# Fastino_FPGA_Config.net
KiCad netlist of a schematic drawn in Altium Designer
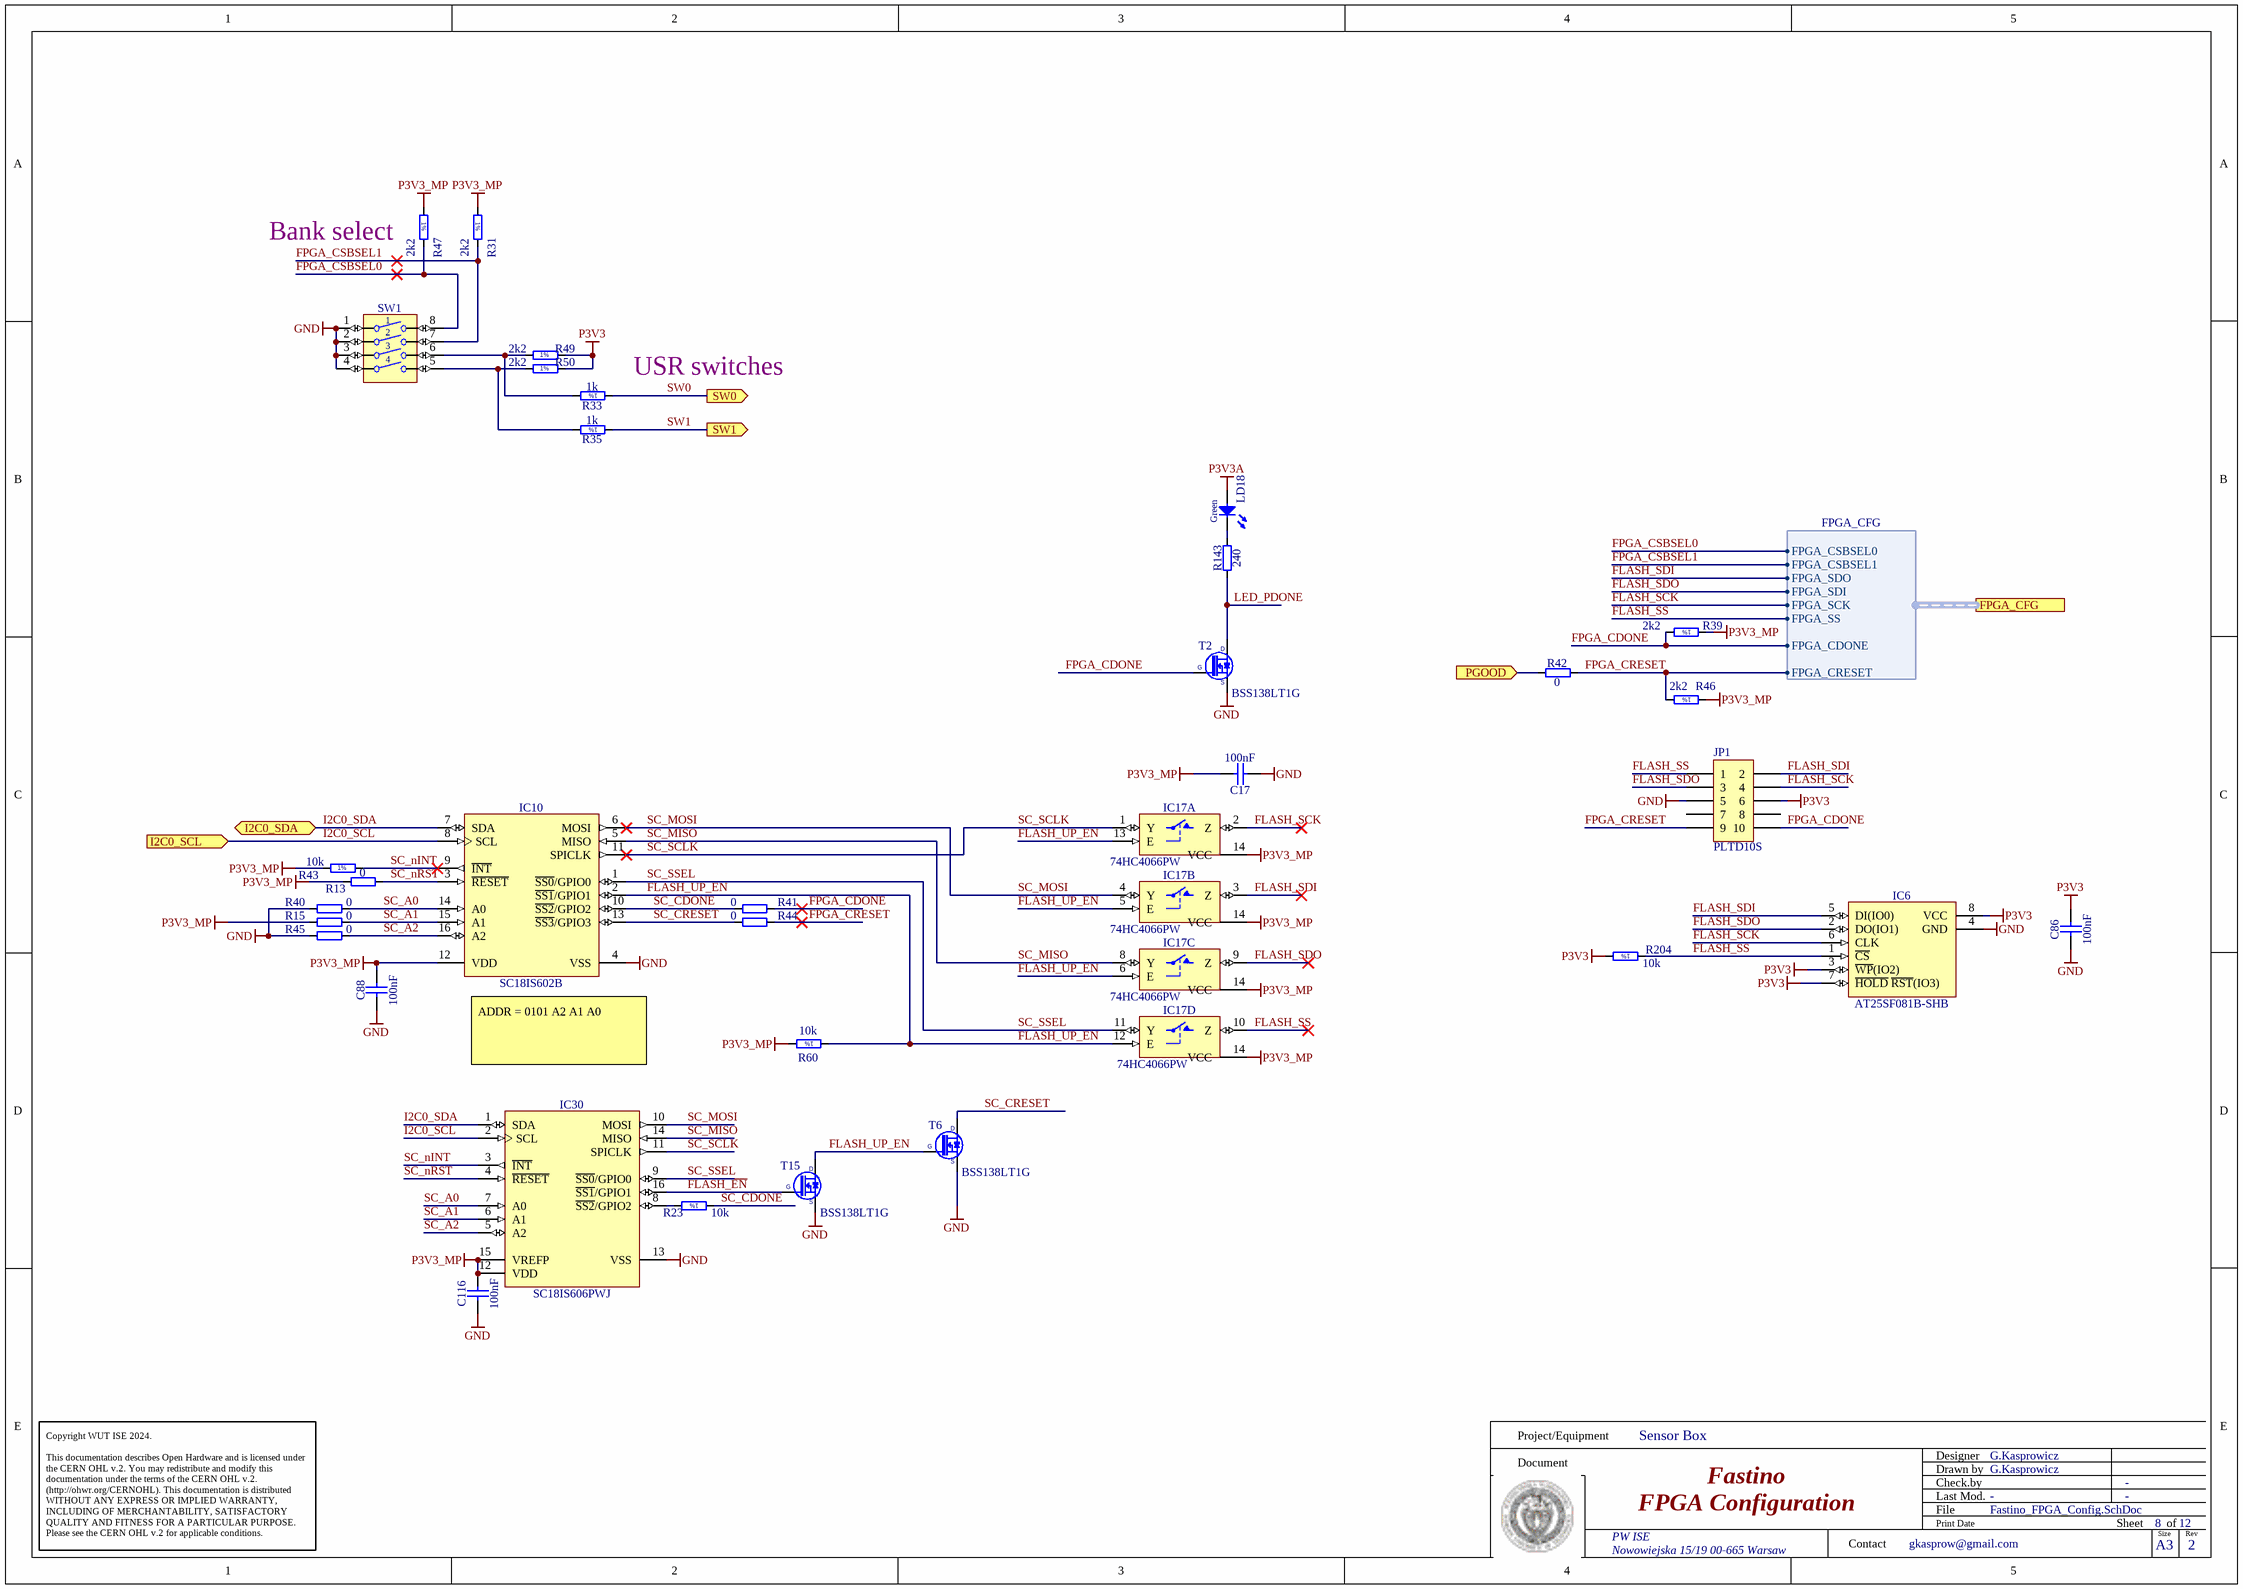
[diagram p0: Fastino_FPGA_Config.SchDoc]

(export (version "E")
  (design (tool "Eeschema 10.0.6"))
  (components
    (comp (ref "C17")
      (value "100nF")
      (footprint "CAPC1005X55N")
      (description "Non-polarised capacitor")
      (fields
        (field (name "PART NUMBER") "CC0402_100NF_16V_10%_X5R")
        (field (name "VOLTAGE") "16V")
        (field (name "AUTHOR") "CERN DEM JLC")
      )
      (libsource (lib "Capacitors") (part "Capacitor - non polarized"))
    )
    (comp (ref "C86")
      (value "100nF")
      (footprint "CAPC1005X55N")
      (description "Non-polarised capacitor")
      (fields
        (field (name "PART NUMBER") "CC0402_100NF_16V_10%_X5R")
        (field (name "VOLTAGE") "16V")
        (field (name "AUTHOR") "CERN DEM JLC")
      )
      (libsource (lib "Capacitors") (part "Capacitor - non polarized"))
    )
    (comp (ref "C88")
      (value "100nF")
      (footprint "CAPC1005X55N")
      (description "Non-polarised capacitor")
      (fields
        (field (name "PART NUMBER") "CC0402_100NF_16V_10%_X5R")
        (field (name "VOLTAGE") "16V")
        (field (name "AUTHOR") "CERN DEM JLC")
      )
      (libsource (lib "Capacitors") (part "Capacitor - non polarized"))
    )
    (comp (ref "C116")
      (value "100nF")
      (footprint "CAPC1005X55N")
      (description "Non-polarised capacitor")
      (fields
        (field (name "PART NUMBER") "CC0402_100NF_16V_10%_X5R")
        (field (name "VOLTAGE") "16V")
        (field (name "AUTHOR") "CERN DEM JLC")
      )
      (libsource (lib "Capacitors") (part "Capacitor - non polarized"))
    )
    (comp (ref "IC6")
      (value "AT25SF081B-SHB")
      (footprint "SOIC127P790X216-8N")
      (description "8M-bit Serial Flash Memory with uniform 4KB sectors and Dual/Quad SPI and QPI")
      (fields (field (name "MANUFACTURER") "Renesas") (field (name "AUTHOR") "GK"))
      (libsource (lib "ICS-logic") (part "MEM_AT25SF081B-SHB"))
    )
    (comp (ref "IC10")
      (value "SC18IS602B")
      (footprint "SOP65P640X110-16N")
      (description "I2C-bus to SPI bridge")
      (fields (field (name "MANUFACTURER") "NXP SEMICONDUCTORS") (field (name "AUTHOR") "CERN DEM MR"))
      (libsource (lib "ICs And Semiconductors") (part "SC18IS602B"))
    )
    (comp (ref "IC17")
      (value "74HC4066PW")
      (footprint "SOP65P640X110-14N")
      (fields (field (name "MANUFACTURER") "NXP SEMICONDUCTORS") (field (name "AUTHOR") "CERN DEM JLC"))
      (libsource (lib "ICs And Semiconductors") (part "4066"))
    )
    (comp (ref "IC30")
      (value "SC18IS606PWJ")
      (footprint "SOP65P640X110-16N")
      (description "I2C-bus to SPI bridge")
      (fields (field (name "MANUFACTURER") "NXP SEMICONDUCTORS") (field (name "AUTHOR") "GK"))
      (libsource (lib "ICS-logic") (part "SC18IS606PWJ"))
    )
    (comp (ref "JP1")
      (value "PLTD10S")
      (footprint "PLTD10S")
      (description "Goldpin 2.54mm, male header")
      (fields (field (name "MANUFACTURER") "Maritex"))
      (libsource (lib "LIBRARY_SCH") (part "CON_2x5 2.54 male SMT"))
    )
    (comp (ref "LD18")
      (value "Green")
      (footprint "LED_AVAGO_HSME-C120")
      (description "LED Green 1C 2A")
      (fields
        (field (name "PART NUMBER") "LED_AVAGO_HSME-C120")
        (field (name "MANUFACTURER") "AVAGO TECHNOLOGIES")
        (field (name "AUTHOR") "CERN DEM JMW")
      )
      (libsource (lib "ICs And Semiconductors") (part "LED Green 1C 2A"))
    )
    (comp (ref "R13")
      (value "0")
      (footprint "RESC1005X40N")
      (description "Resistor")
      (fields
        (field (name "PART NUMBER") "R0402_0R_JUMPER")
        (field (name "MANUFACTURER") "GENERIC")
        (field (name "AUTHOR") "CERN DEM JLC")
      )
      (libsource (lib "Resistors") (part "Resistor"))
    )
    (comp (ref "R15")
      (value "0")
      (footprint "RESC1005X40N")
      (description "Resistor")
      (fields
        (field (name "PART NUMBER") "R0402_0R_JUMPER")
        (field (name "MANUFACTURER") "GENERIC")
        (field (name "AUTHOR") "CERN DEM JLC")
      )
      (libsource (lib "Resistors") (part "Resistor"))
    )
    (comp (ref "R23")
      (value "10k")
      (footprint "RESC1005X40N")
      (description "Resistor - 1%")
      (fields
        (field (name "PART NUMBER") "R0402_10K_1%_0.0625W_100PPM")
        (field (name "POWER") "0.0625W")
        (field (name "AUTHOR") "CERN DEM JLC")
      )
      (libsource (lib "Resistors") (part "Resistor - 1%"))
    )
    (comp (ref "R31")
      (value "2k2")
      (footprint "RESC1005X40N")
      (description "Resistor - 1%")
      (fields
        (field (name "PART NUMBER") "R0402_2K2_1%_0.0625W_100PPM")
        (field (name "POWER") "0.0625W")
        (field (name "AUTHOR") "CERN DEM JLC")
      )
      (libsource (lib "Resistors") (part "Resistor - 1%"))
    )
    (comp (ref "R33")
      (value "1k")
      (footprint "RESC1005X40N")
      (description "Resistor - 1%")
      (fields
        (field (name "PART NUMBER") "R0402_1K_1%_0.0625W_100PPM")
        (field (name "POWER") "0.0625W")
        (field (name "AUTHOR") "CERN DEM JLC")
      )
      (libsource (lib "Resistors") (part "Resistor - 1%"))
    )
    (comp (ref "R35")
      (value "1k")
      (footprint "RESC1005X40N")
      (description "Resistor - 1%")
      (fields
        (field (name "PART NUMBER") "R0402_1K_1%_0.0625W_100PPM")
        (field (name "POWER") "0.0625W")
        (field (name "AUTHOR") "CERN DEM JLC")
      )
      (libsource (lib "Resistors") (part "Resistor - 1%"))
    )
    (comp (ref "R39")
      (value "2k2")
      (footprint "RESC1005X40N")
      (description "Resistor - 1%")
      (fields
        (field (name "PART NUMBER") "R0402_2K2_1%_0.0625W_100PPM")
        (field (name "POWER") "0.0625W")
        (field (name "AUTHOR") "CERN DEM JLC")
      )
      (libsource (lib "Resistors") (part "Resistor - 1%"))
    )
    (comp (ref "R40")
      (value "0")
      (footprint "RESC1005X40N")
      (description "Resistor")
      (fields
        (field (name "PART NUMBER") "R0402_0R_JUMPER")
        (field (name "MANUFACTURER") "GENERIC")
        (field (name "AUTHOR") "CERN DEM JLC")
      )
      (libsource (lib "Resistors") (part "Resistor"))
    )
    (comp (ref "R41")
      (value "0")
      (footprint "RESC1005X40N")
      (description "Resistor")
      (fields
        (field (name "PART NUMBER") "R0402_0R_JUMPER")
        (field (name "MANUFACTURER") "GENERIC")
        (field (name "AUTHOR") "CERN DEM JLC")
      )
      (libsource (lib "Resistors") (part "Resistor"))
    )
    (comp (ref "R42")
      (value "0")
      (footprint "RESC1005X40N")
      (description "Resistor")
      (fields
        (field (name "PART NUMBER") "R0402_0R_JUMPER")
        (field (name "MANUFACTURER") "GENERIC")
        (field (name "AUTHOR") "CERN DEM JLC")
      )
      (libsource (lib "Resistors") (part "Resistor"))
    )
    (comp (ref "R43")
      (value "10k")
      (footprint "RESC1005X40N")
      (description "Resistor - 1%")
      (fields
        (field (name "PART NUMBER") "R0402_10K_1%_0.0625W_100PPM")
        (field (name "POWER") "0.0625W")
        (field (name "AUTHOR") "CERN DEM JLC")
      )
      (libsource (lib "Resistors") (part "Resistor - 1%"))
    )
    (comp (ref "R44")
      (value "0")
      (footprint "RESC1005X40N")
      (description "Resistor")
      (fields
        (field (name "PART NUMBER") "R0402_0R_JUMPER")
        (field (name "MANUFACTURER") "GENERIC")
        (field (name "AUTHOR") "CERN DEM JLC")
      )
      (libsource (lib "Resistors") (part "Resistor"))
    )
    (comp (ref "R45")
      (value "0")
      (footprint "RESC1005X40N")
      (description "Resistor")
      (fields
        (field (name "PART NUMBER") "R0402_0R_JUMPER")
        (field (name "MANUFACTURER") "GENERIC")
        (field (name "AUTHOR") "CERN DEM JLC")
      )
      (libsource (lib "Resistors") (part "Resistor"))
    )
    (comp (ref "R46")
      (value "2k2")
      (footprint "RESC1005X40N")
      (description "Resistor - 1%")
      (fields
        (field (name "PART NUMBER") "R0402_2K2_1%_0.0625W_100PPM")
        (field (name "POWER") "0.0625W")
        (field (name "AUTHOR") "CERN DEM JLC")
      )
      (libsource (lib "Resistors") (part "Resistor - 1%"))
    )
    (comp (ref "R47")
      (value "2k2")
      (footprint "RESC1005X40N")
      (description "Resistor - 1%")
      (fields
        (field (name "PART NUMBER") "R0402_2K2_1%_0.0625W_100PPM")
        (field (name "POWER") "0.0625W")
        (field (name "AUTHOR") "CERN DEM JLC")
      )
      (libsource (lib "Resistors") (part "Resistor - 1%"))
    )
    (comp (ref "R49")
      (value "2k2")
      (footprint "RESC1005X40N")
      (description "Resistor - 1%")
      (fields
        (field (name "PART NUMBER") "R0402_2K2_1%_0.0625W_100PPM")
        (field (name "POWER") "0.0625W")
        (field (name "AUTHOR") "CERN DEM JLC")
      )
      (libsource (lib "Resistors") (part "Resistor - 1%"))
    )
    (comp (ref "R50")
      (value "2k2")
      (footprint "RESC1005X40N")
      (description "Resistor - 1%")
      (fields
        (field (name "PART NUMBER") "R0402_2K2_1%_0.0625W_100PPM")
        (field (name "POWER") "0.0625W")
        (field (name "AUTHOR") "CERN DEM JLC")
      )
      (libsource (lib "Resistors") (part "Resistor - 1%"))
    )
    (comp (ref "R60")
      (value "10k")
      (footprint "RESC1005X40N")
      (description "Resistor - 1%")
      (fields
        (field (name "PART NUMBER") "R0402_10K_1%_0.0625W_100PPM")
        (field (name "POWER") "0.0625W")
        (field (name "AUTHOR") "CERN DEM JLC")
      )
      (libsource (lib "Resistors") (part "Resistor - 1%"))
    )
    (comp (ref "R143")
      (value "240")
      (footprint "RESC1005X40N")
      (description "Resistor - 1%")
      (fields
        (field (name "PART NUMBER") "R0402_240R_1%_0.0625W_100PPM")
        (field (name "POWER") "0.0625W")
        (field (name "AUTHOR") "CERN DEM JLC")
      )
      (libsource (lib "Resistors") (part "Resistor - 1%"))
    )
    (comp (ref "R204")
      (value "10k")
      (footprint "RESC1005X40N")
      (description "Resistor - 1%")
      (fields
        (field (name "PART NUMBER") "R0402_10K_1%_0.0625W_100PPM")
        (field (name "POWER") "0.0625W")
        (field (name "AUTHOR") "CERN DEM JLC")
      )
      (libsource (lib "Resistors") (part "Resistor - 1%"))
    )
    (comp (ref "SW1")
      (value "Switch")
      (footprint "SW_TYCO_1571983-4")
      (description "4 Ways SPST DIP Switch")
      (fields
        (field (name "PART NUMBER") "SW_TYCO_1571983-4")
        (field (name "MANUFACTURER") "TYCO")
        (field (name "AUTHOR") "CERN DEM JLC")
      )
      (libsource (lib "Eletro-mechanical") (part "SW 4x SPST DIP Switch"))
    )
    (comp (ref "T2")
      (value "BSS138LT1G")
      (footprint "SOT95P240X110-3N")
      (description "N-CHANNEL MOSFET WITH DIODE")
      (fields (field (name "MANUFACTURER") "ON SEMICONDUCTOR") (field (name "AUTHOR") "CERN DEM JLC"))
      (libsource (lib "ICs And Semiconductors") (part "N-MOSFET-D 1G 2S 3D"))
    )
    (comp (ref "T6")
      (value "BSS138LT1G")
      (footprint "SOT95P240X110-3N")
      (description "N-CHANNEL MOSFET WITH DIODE")
      (fields (field (name "MANUFACTURER") "ON SEMICONDUCTOR") (field (name "AUTHOR") "CERN DEM JLC"))
      (libsource (lib "ICs And Semiconductors") (part "N-MOSFET-D 1G 2S 3D"))
    )
    (comp (ref "T15")
      (value "BSS138LT1G")
      (footprint "SOT95P240X110-3N")
      (description "N-CHANNEL MOSFET WITH DIODE")
      (fields (field (name "MANUFACTURER") "ON SEMICONDUCTOR") (field (name "AUTHOR") "CERN DEM JLC"))
      (libsource (lib "ICs And Semiconductors") (part "N-MOSFET-D 1G 2S 3D"))
    )
  )
  (nets
    (net (code "2") (name "/FLASH_SCK") (class "Default")
      (node (ref "IC17") (pin "2") (pinfunction "Z_2") (pintype "bidirectional"))
      (node (ref "IC6") (pin "6") (pinfunction "CLK_6") (pintype "input"))
      (node (ref "JP1") (pin "4") (pinfunction "4_4") (pintype "passive"))
    )
    (net (code "3") (name "/FLASH_SDI") (class "Default")
      (node (ref "IC17") (pin "3") (pinfunction "Z_3") (pintype "bidirectional"))
      (node (ref "IC6") (pin "5") (pinfunction "DI(IO0)_5") (pintype "bidirectional"))
      (node (ref "JP1") (pin "2") (pinfunction "2_2") (pintype "passive"))
    )
    (net (code "4") (name "/FLASH_SDO") (class "Default")
      (node (ref "IC17") (pin "9") (pinfunction "Z_9") (pintype "bidirectional"))
      (node (ref "IC6") (pin "2") (pinfunction "DO(IO1)_2") (pintype "bidirectional"))
      (node (ref "JP1") (pin "3") (pinfunction "3_3") (pintype "passive"))
    )
    (net (code "5") (name "/FLASH_SS") (class "Default")
      (node (ref "IC17") (pin "10") (pinfunction "Z_10") (pintype "bidirectional"))
      (node (ref "IC6") (pin "1") (pinfunction "~{CS}_1") (pintype "input"))
      (node (ref "JP1") (pin "1") (pinfunction "1_1") (pintype "passive"))
      (node (ref "R204") (pin "1") (pinfunction "1_1") (pintype "passive"))
    )
    (net (code "6") (name "/FLASH_UP_EN") (class "Default")
      (node (ref "IC10") (pin "2") (pinfunction "~{SS1}/GPIO1_2") (pintype "bidirectional"))
      (node (ref "IC17") (pin "12") (pinfunction "E_12") (pintype "input"))
      (node (ref "IC17") (pin "13") (pinfunction "E_13") (pintype "input"))
      (node (ref "IC17") (pin "5") (pinfunction "E_5") (pintype "input"))
      (node (ref "IC17") (pin "6") (pinfunction "E_6") (pintype "input"))
      (node (ref "R60") (pin "1") (pinfunction "1_1") (pintype "passive"))
      (node (ref "T15") (pin "3") (pinfunction "D_3") (pintype "passive"))
      (node (ref "T6") (pin "1") (pinfunction "G_1") (pintype "passive"))
    )
    (net (code "7") (name "/FPGA_CDONE") (class "Default")
      (node (ref "JP1") (pin "10") (pinfunction "10_10") (pintype "passive"))
      (node (ref "R39") (pin "2") (pinfunction "2_2") (pintype "passive"))
      (node (ref "R41") (pin "1") (pinfunction "1_1") (pintype "passive"))
      (node (ref "T2") (pin "1") (pinfunction "G_1") (pintype "passive"))
    )
    (net (code "8") (name "/FPGA_CRESET") (class "Default")
      (node (ref "JP1") (pin "9") (pinfunction "9_9") (pintype "passive"))
      (node (ref "R42") (pin "2") (pinfunction "2_2") (pintype "passive"))
      (node (ref "R44") (pin "1") (pinfunction "1_1") (pintype "passive"))
      (node (ref "R46") (pin "2") (pinfunction "2_2") (pintype "passive"))
    )
    (net (code "9") (name "/FPGA_CSBSEL0") (class "Default")
      (node (ref "R47") (pin "2") (pinfunction "2_2") (pintype "passive"))
      (node (ref "SW1") (pin "8") (pinfunction "8_8") (pintype "bidirectional"))
    )
    (net (code "10") (name "/FPGA_CSBSEL1") (class "Default")
      (node (ref "R31") (pin "2") (pinfunction "2_2") (pintype "passive"))
      (node (ref "SW1") (pin "7") (pinfunction "7_7") (pintype "bidirectional"))
    )
    (net (code "11") (name "/I2C0_SCL") (class "Default")
      (node (ref "IC10") (pin "8") (pinfunction "SCL_8") (pintype "input"))
      (node (ref "IC30") (pin "2") (pinfunction "SCL_2") (pintype "input"))
    )
    (net (code "12") (name "/I2C0_SDA") (class "Default")
      (node (ref "IC10") (pin "7") (pinfunction "SDA_7") (pintype "bidirectional"))
      (node (ref "IC30") (pin "1") (pinfunction "SDA_1") (pintype "bidirectional"))
    )
    (net (code "13") (name "/LED_PDONE") (class "Default")
      (node (ref "R143") (pin "1") (pinfunction "1_1") (pintype "passive"))
      (node (ref "T2") (pin "3") (pinfunction "D_3") (pintype "passive"))
    )
    (net (code "14") (name "/PGOOD") (class "Default")
      (node (ref "R42") (pin "1") (pinfunction "1_1") (pintype "passive"))
    )
    (net (code "15") (name "/SC_A0") (class "Default")
      (node (ref "IC10") (pin "14") (pinfunction "A0_14") (pintype "input"))
      (node (ref "IC30") (pin "7") (pinfunction "A0_7") (pintype "input"))
      (node (ref "R40") (pin "1") (pinfunction "1_1") (pintype "passive"))
    )
    (net (code "16") (name "/SC_A1") (class "Default")
      (node (ref "IC10") (pin "15") (pinfunction "A1_15") (pintype "input"))
      (node (ref "IC30") (pin "6") (pinfunction "A1_6") (pintype "input"))
      (node (ref "R15") (pin "1") (pinfunction "1_1") (pintype "passive"))
    )
    (net (code "17") (name "/SC_A2") (class "Default")
      (node (ref "IC10") (pin "16") (pinfunction "A2_16") (pintype "bidirectional"))
      (node (ref "IC30") (pin "5") (pinfunction "A2_5") (pintype "bidirectional"))
      (node (ref "R45") (pin "1") (pinfunction "1_1") (pintype "passive"))
    )
    (net (code "18") (name "/SC_CDONE") (class "Default")
      (node (ref "IC10") (pin "10") (pinfunction "~{SS2}/GPIO2_10") (pintype "bidirectional"))
      (node (ref "R23") (pin "1") (pinfunction "1_1") (pintype "passive"))
      (node (ref "R41") (pin "2") (pinfunction "2_2") (pintype "passive"))
    )
    (net (code "19") (name "/SC_CRESET") (class "Default")
      (node (ref "IC10") (pin "13") (pinfunction "~{SS3}/GPIO3_13") (pintype "bidirectional"))
      (node (ref "R44") (pin "2") (pinfunction "2_2") (pintype "passive"))
      (node (ref "T6") (pin "3") (pinfunction "D_3") (pintype "passive"))
    )
    (net (code "20") (name "/SC_MISO") (class "Default")
      (node (ref "IC10") (pin "5") (pinfunction "MISO_5") (pintype "input"))
      (node (ref "IC17") (pin "8") (pinfunction "Y_8") (pintype "bidirectional"))
      (node (ref "IC30") (pin "14") (pinfunction "MISO_14") (pintype "input"))
    )
    (net (code "21") (name "/SC_MOSI") (class "Default")
      (node (ref "IC10") (pin "6") (pinfunction "MOSI_6") (pintype "output"))
      (node (ref "IC17") (pin "4") (pinfunction "Y_4") (pintype "bidirectional"))
      (node (ref "IC30") (pin "10") (pinfunction "MOSI_10") (pintype "output"))
    )
    (net (code "22") (name "/SC_SCLK") (class "Default")
      (node (ref "IC10") (pin "11") (pinfunction "SPICLK_11") (pintype "output"))
      (node (ref "IC17") (pin "1") (pinfunction "Y_1") (pintype "bidirectional"))
      (node (ref "IC30") (pin "11") (pinfunction "SPICLK_11") (pintype "output"))
    )
    (net (code "23") (name "/SC_SSEL") (class "Default")
      (node (ref "IC10") (pin "1") (pinfunction "~{SS0}/GPIO0_1") (pintype "bidirectional"))
      (node (ref "IC17") (pin "11") (pinfunction "Y_11") (pintype "bidirectional"))
      (node (ref "IC30") (pin "9") (pinfunction "~{SS0}/GPIO0_9") (pintype "bidirectional"))
    )
    (net (code "24") (name "/SC_nINT") (class "Default")
      (node (ref "IC10") (pin "9") (pinfunction "~{INT}_9") (pintype "output"))
      (node (ref "IC30") (pin "3") (pinfunction "~{INT}_3") (pintype "output"))
      (node (ref "R43") (pin "2") (pinfunction "2_2") (pintype "passive"))
    )
    (net (code "25") (name "/SC_nRST") (class "Default")
      (node (ref "IC10") (pin "3") (pinfunction "~{RESET}_3") (pintype "input"))
      (node (ref "IC30") (pin "4") (pinfunction "~{RESET}_4") (pintype "input"))
      (node (ref "R13") (pin "1") (pinfunction "1_1") (pintype "passive"))
    )
    (net (code "26") (name "/SW0") (class "Default")
      (node (ref "R33") (pin "1") (pinfunction "1_1") (pintype "passive"))
    )
    (net (code "27") (name "/SW1") (class "Default")
      (node (ref "R35") (pin "1") (pinfunction "1_1") (pintype "passive"))
    )
    (net (code "29") (name "/~{FLASH_EN}") (class "Default")
      (node (ref "IC30") (pin "16") (pinfunction "~{SS1}/GPIO1_16") (pintype "bidirectional"))
      (node (ref "T15") (pin "1") (pinfunction "G_1") (pintype "passive"))
    )
    (net (code "30") (name "GND") (class "Default")
      (node (ref "C116") (pin "1") (pinfunction "1_1") (pintype "passive"))
      (node (ref "C17") (pin "1") (pinfunction "1_1") (pintype "passive"))
      (node (ref "C86") (pin "1") (pinfunction "1_1") (pintype "passive"))
      (node (ref "C88") (pin "1") (pinfunction "1_1") (pintype "passive"))
      (node (ref "IC10") (pin "4") (pinfunction "VSS_4") (pintype "power_in"))
      (node (ref "IC17") (pin "7") (pinfunction "GND_7") (pintype "power_in"))
      (node (ref "IC30") (pin "13") (pinfunction "VSS_13") (pintype "power_in"))
      (node (ref "IC6") (pin "4") (pinfunction "GND_4") (pintype "power_in"))
      (node (ref "JP1") (pin "5") (pinfunction "5_5") (pintype "passive"))
      (node (ref "R40") (pin "2") (pinfunction "2_2") (pintype "passive"))
      (node (ref "R45") (pin "2") (pinfunction "2_2") (pintype "passive"))
      (node (ref "SW1") (pin "1") (pinfunction "1_1") (pintype "bidirectional"))
      (node (ref "SW1") (pin "2") (pinfunction "2_2") (pintype "bidirectional"))
      (node (ref "SW1") (pin "3") (pinfunction "3_3") (pintype "bidirectional"))
      (node (ref "SW1") (pin "4") (pinfunction "4_4") (pintype "bidirectional"))
      (node (ref "T15") (pin "2") (pinfunction "S_2") (pintype "passive"))
      (node (ref "T2") (pin "2") (pinfunction "S_2") (pintype "passive"))
      (node (ref "T6") (pin "2") (pinfunction "S_2") (pintype "passive"))
    )
    (net (code "31") (name "Net-(IC30-~{SS2}{slash}GPIO2)") (class "Default")
      (node (ref "IC30") (pin "8") (pinfunction "~{SS2}/GPIO2_8") (pintype "bidirectional"))
      (node (ref "R23") (pin "2") (pinfunction "2_2") (pintype "passive"))
    )
    (net (code "32") (name "Net-(LD18-C)") (class "Default")
      (node (ref "LD18") (pin "1") (pinfunction "C_1") (pintype "passive"))
      (node (ref "R143") (pin "2") (pinfunction "2_2") (pintype "passive"))
    )
    (net (code "33") (name "Net-(R33-Pad2)") (class "Default")
      (node (ref "R33") (pin "2") (pinfunction "2_2") (pintype "passive"))
      (node (ref "R49") (pin "1") (pinfunction "1_1") (pintype "passive"))
      (node (ref "SW1") (pin "6") (pinfunction "6_6") (pintype "bidirectional"))
    )
    (net (code "34") (name "Net-(R35-Pad2)") (class "Default")
      (node (ref "R35") (pin "2") (pinfunction "2_2") (pintype "passive"))
      (node (ref "R50") (pin "1") (pinfunction "1_1") (pintype "passive"))
      (node (ref "SW1") (pin "5") (pinfunction "5_5") (pintype "bidirectional"))
    )
    (net (code "35") (name "P3V3") (class "Default")
      (node (ref "C86") (pin "2") (pinfunction "2_2") (pintype "passive"))
      (node (ref "IC6") (pin "3") (pinfunction "~{WP}(IO2)_3") (pintype "bidirectional"))
      (node (ref "IC6") (pin "7") (pinfunction "~{HOLD}_~{RST}(IO3)_7") (pintype "bidirectional"))
      (node (ref "IC6") (pin "8") (pinfunction "VCC_8") (pintype "power_in"))
      (node (ref "JP1") (pin "6") (pinfunction "6_6") (pintype "passive"))
      (node (ref "R204") (pin "2") (pinfunction "2_2") (pintype "passive"))
      (node (ref "R49") (pin "2") (pinfunction "2_2") (pintype "passive"))
      (node (ref "R50") (pin "2") (pinfunction "2_2") (pintype "passive"))
    )
    (net (code "36") (name "P3V3A") (class "Default")
      (node (ref "LD18") (pin "2") (pinfunction "A_2") (pintype "passive"))
    )
    (net (code "37") (name "P3V3_MP") (class "Default")
      (node (ref "C116") (pin "2") (pinfunction "2_2") (pintype "passive"))
      (node (ref "C17") (pin "2") (pinfunction "2_2") (pintype "passive"))
      (node (ref "C88") (pin "2") (pinfunction "2_2") (pintype "passive"))
      (node (ref "IC10") (pin "12") (pinfunction "VDD_12") (pintype "power_in"))
      (node (ref "IC17") (pin "14") (pinfunction "VCC_14") (pintype "power_in"))
      (node (ref "IC30") (pin "12") (pinfunction "VDD_12") (pintype "power_in"))
      (node (ref "IC30") (pin "15") (pinfunction "VREFP_15") (pintype "power_in"))
      (node (ref "R13") (pin "2") (pinfunction "2_2") (pintype "passive"))
      (node (ref "R15") (pin "2") (pinfunction "2_2") (pintype "passive"))
      (node (ref "R31") (pin "1") (pinfunction "1_1") (pintype "passive"))
      (node (ref "R39") (pin "1") (pinfunction "1_1") (pintype "passive"))
      (node (ref "R43") (pin "1") (pinfunction "1_1") (pintype "passive"))
      (node (ref "R46") (pin "1") (pinfunction "1_1") (pintype "passive"))
      (node (ref "R47") (pin "1") (pinfunction "1_1") (pintype "passive"))
      (node (ref "R60") (pin "2") (pinfunction "2_2") (pintype "passive"))
    )
    (net (code "38") (name "unconnected-(JP1-Pad7)") (class "Default")
      (node (ref "JP1") (pin "7") (pinfunction "7_7") (pintype "passive"))
    )
    (net (code "39") (name "unconnected-(JP1-Pad8)") (class "Default")
      (node (ref "JP1") (pin "8") (pinfunction "8_8") (pintype "passive"))
    )
  )
)
